# USB.net
KiCad netlist of a schematic drawn in Altium Designer
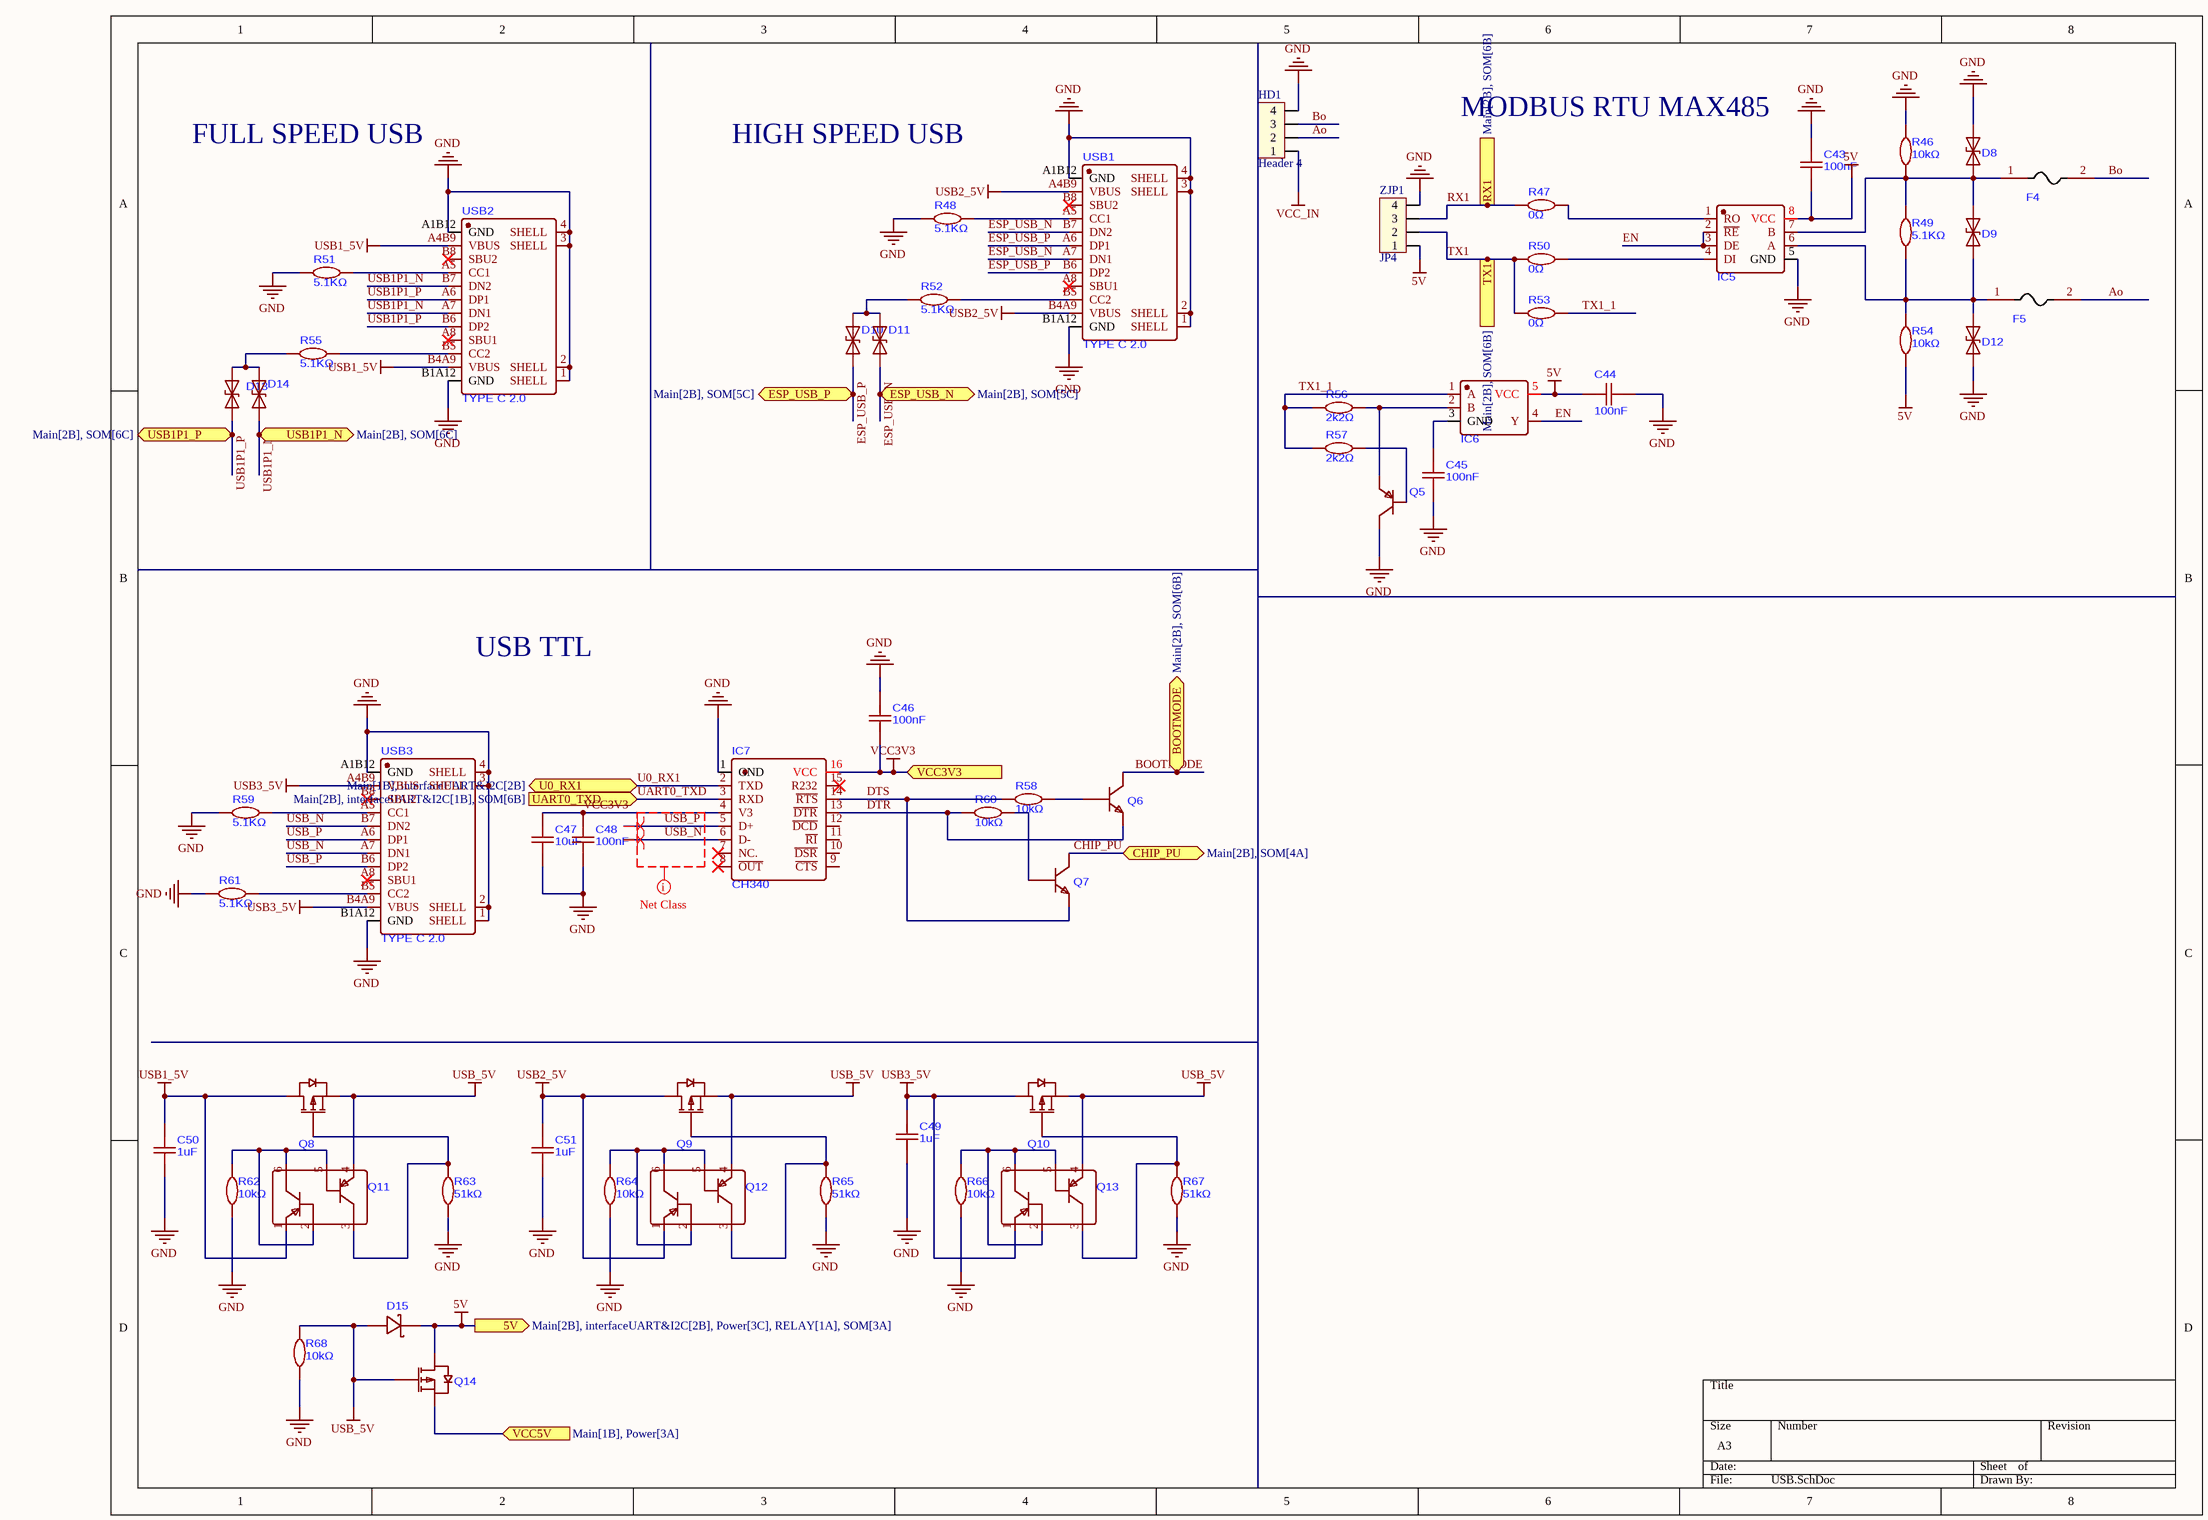
[diagram p0: USB.SchDoc]

(export (version "E")
  (design (tool "Eeschema 10.0.6"))
  (components
    (comp (ref "C43")
      (value "100nF")
      (footprint "C0603")
      (description "50V 100nF X7R ±10% 0603 Ceramic Capacitors ROHS")
      (libsource (lib "Schlib2") (part "CC0603KRX7R9BB104"))
    )
    (comp (ref "C44")
      (value "100nF")
      (footprint "C0603")
      (description "50V 100nF X7R ±10% 0603 Ceramic Capacitors ROHS")
      (libsource (lib "Schlib2") (part "CC0603KRX7R9BB104"))
    )
    (comp (ref "C45")
      (value "100nF")
      (footprint "C0603")
      (description "50V 100nF X7R ±10% 0603 Ceramic Capacitors ROHS")
      (libsource (lib "Schlib2") (part "CC0603KRX7R9BB104"))
    )
    (comp (ref "C46")
      (value "100nF")
      (footprint "C0603")
      (description "50V 100nF X7R ±10% 0603 Ceramic Capacitors ROHS")
      (libsource (lib "Schlib2") (part "CC0603KRX7R9BB104"))
    )
    (comp (ref "C47")
      (value "10uF")
      (footprint "C0603")
      (description "25V 10uF X5R ±20% 0603 Ceramic Capacitors ROHS")
      (libsource (lib "Schlib2") (part "CL10A106MA8NRNC"))
    )
    (comp (ref "C48")
      (value "100nF")
      (footprint "C0603")
      (description "50V 100nF X7R ±10% 0603 Ceramic Capacitors ROHS")
      (libsource (lib "Schlib2") (part "CC0603KRX7R9BB104"))
    )
    (comp (ref "C49")
      (value "1uF")
      (footprint "C0603")
      (description "25V 1uF X7R ±10% 0603 Ceramic Capacitors ROHS")
      (libsource (lib "Schlib2") (part "CL10B105KA8NNNC"))
    )
    (comp (ref "C50")
      (value "1uF")
      (footprint "C0603")
      (description "25V 1uF X7R ±10% 0603 Ceramic Capacitors ROHS")
      (libsource (lib "Schlib2") (part "CL10B105KA8NNNC"))
    )
    (comp (ref "C51")
      (value "1uF")
      (footprint "C0603")
      (description "25V 1uF X7R ±10% 0603 Ceramic Capacitors ROHS")
      (libsource (lib "Schlib2") (part "CL10B105KA8NNNC"))
    )
    (comp (ref "D8")
      (value "TVS DIODE 5VWM 18.6VC SOD-523")
      (footprint "SOD-523_L1.2-W0.8-LS1.6-BI")
      (description "9.4A@8/20us 18.6V 7.8V 5V SOD-523 TVS Diodes RoHS")
      (libsource (lib "Schlib2") (part "LESD5D5.0CT1G"))
    )
    (comp (ref "D9")
      (value "TVS DIODE 5VWM 18.6VC SOD-523")
      (footprint "SOD-523_L1.2-W0.8-LS1.6-BI")
      (description "9.4A@8/20us 18.6V 7.8V 5V SOD-523 TVS Diodes RoHS")
      (libsource (lib "Schlib2") (part "LESD5D5.0CT1G"))
    )
    (comp (ref "D10")
      (value "TVS DIODE 5VWM 18.6VC SOD-523")
      (footprint "SOD-523_L1.2-W0.8-LS1.6-BI")
      (description "9.4A@8/20us 18.6V 7.8V 5V SOD-523 TVS Diodes RoHS")
      (libsource (lib "Schlib2") (part "LESD5D5.0CT1G"))
    )
    (comp (ref "D11")
      (value "TVS DIODE 5VWM 18.6VC SOD-523")
      (footprint "SOD-523_L1.2-W0.8-LS1.6-BI")
      (description "9.4A@8/20us 18.6V 7.8V 5V SOD-523 TVS Diodes RoHS")
      (libsource (lib "Schlib2") (part "LESD5D5.0CT1G"))
    )
    (comp (ref "D12")
      (value "TVS DIODE 5VWM 18.6VC SOD-523")
      (footprint "SOD-523_L1.2-W0.8-LS1.6-BI")
      (description "9.4A@8/20us 18.6V 7.8V 5V SOD-523 TVS Diodes RoHS")
      (libsource (lib "Schlib2") (part "LESD5D5.0CT1G"))
    )
    (comp (ref "D13")
      (value "TVS DIODE 5VWM 18.6VC SOD-523")
      (footprint "SOD-523_L1.2-W0.8-LS1.6-BI")
      (description "9.4A@8/20us 18.6V 7.8V 5V SOD-523 TVS Diodes RoHS")
      (libsource (lib "Schlib2") (part "LESD5D5.0CT1G"))
    )
    (comp (ref "D14")
      (value "TVS DIODE 5VWM 18.6VC SOD-523")
      (footprint "SOD-523_L1.2-W0.8-LS1.6-BI")
      (description "9.4A@8/20us 18.6V 7.8V 5V SOD-523 TVS Diodes RoHS")
      (libsource (lib "Schlib2") (part "LESD5D5.0CT1G"))
    )
    (comp (ref "D15")
      (value "B540CQ-13-F")
      (footprint "SMC_L6.9-W5.9-LS7.9-RD")
      (description "40V 550mV@5A 5A SMC(DO-214AB) Single Diodes ROHS")
      (libsource (lib "Schlib2") (part "B540CQ-13-F"))
    )
    (comp (ref "F4")
      (value "PTC RESET FUSE 24V 100mA 0603")
      (footprint "F0603")
      (description "24V 100mA 40A 300mA 900mΩ 0603 PTC Resettable Fuses RoHS")
      (libsource (lib "Schlib2") (part "0603-010-24V"))
    )
    (comp (ref "F5")
      (value "PTC RESET FUSE 24V 100mA 0603")
      (footprint "F0603")
      (description "24V 100mA 40A 300mA 900mΩ 0603 PTC Resettable Fuses RoHS")
      (libsource (lib "Schlib2") (part "0603-010-24V"))
    )
    (comp (ref "HD1")
      (value "Header 4")
      (footprint "HED4")
      (description "Header 4 (Green)")
      (libsource (lib "syhaunguyen") (part "Hed4"))
    )
    (comp (ref "IC5")
      (value "Low-Power, Slew-Rate-Limited RS-485/RS-422 Transceivers")
      (footprint "SOP-8_L4.9-W3.9-P1.27-LS6.0-BL")
      (description "Transceiver 4.75V~5.25V SOIC-8 Drivers, Receivers, Transceivers RoHS")
      (libsource (lib "Schlib2") (part "MAX485ESA+T_C41365333"))
    )
    (comp (ref "IC6")
      (value "SINGLE 2-INPUT NAND GATE WITH SCHMITT-TRIGGER INPUTS")
      (footprint "SOT-23-5_L3.0-W1.7-P0.95-LS2.8-BL")
      (description "5ns@5V,50pF 10uA 1.65V~5.5V NAND Gate SOT-23-5 Gates and Inverters RoHS")
      (libsource (lib "Schlib2") (part "TP74LVC1G132S5"))
    )
    (comp (ref "IC7")
      (value "CH340")
      (footprint "SOP-16_L10.0-W3.9-P1.27-LS6.0-BL")
      (description "Transceiver USB 2.0 SOP-16 Interface Controllers RoHS")
      (libsource (lib "Schlib2") (part "CH340C"))
    )
    (comp (ref "Q5")
      (value "TRANS PNP 25V 1.5A SOT-23")
      (footprint "SOT-23-3_L2.9-W1.3-P1.90-LS2.4-BR")
      (description "300mW 25V 1.5A PNP SOT-23 Single Bipolar Transistors RoHS")
      (libsource (lib "Schlib2") (part "SS8550_C7420371"))
    )
    (comp (ref "Q6")
      (value "TRANS NPN 25V 0.5A SOT-23")
      (footprint "SOT-23-3_L2.9-W1.3-P1.90-LS2.4-BR")
      (description "300mW 25V 500mA NPN SOT-23 Single Bipolar Transistors RoHS")
      (libsource (lib "Schlib2") (part "S8050_C2828466"))
    )
    (comp (ref "Q7")
      (value "TRANS NPN 25V 0.5A SOT-23")
      (footprint "SOT-23-3_L2.9-W1.3-P1.90-LS2.4-BR")
      (description "300mW 25V 500mA NPN SOT-23 Single Bipolar Transistors RoHS")
      (libsource (lib "Schlib2") (part "S8050_C2828466"))
    )
    (comp (ref "Q8")
      (value "MOSFET P-CH 30V 4.3A SOT-23")
      (footprint "SOT-23-3_L2.9-W1.6-P1.90-LS2.8-BR")
      (description "30V 4.3A 48mΩ@10V 2.5V@250uA 1 P-Channel SOT-23 Single FETs, MOSFETs ROHS")
      (libsource (lib "Schlib2") (part "AO3407A"))
    )
    (comp (ref "Q9")
      (value "MOSFET P-CH 30V 4.3A SOT-23")
      (footprint "SOT-23-3_L2.9-W1.6-P1.90-LS2.8-BR")
      (description "30V 4.3A 48mΩ@10V 2.5V@250uA 1 P-Channel SOT-23 Single FETs, MOSFETs ROHS")
      (libsource (lib "Schlib2") (part "AO3407A"))
    )
    (comp (ref "Q10")
      (value "MOSFET P-CH 30V 4.3A SOT-23")
      (footprint "SOT-23-3_L2.9-W1.6-P1.90-LS2.8-BR")
      (description "30V 4.3A 48mΩ@10V 2.5V@250uA 1 P-Channel SOT-23 Single FETs, MOSFETs ROHS")
      (libsource (lib "Schlib2") (part "AO3407A"))
    )
    (comp (ref "Q11")
      (value "TRANS PNP 40V 200mA SOT-363")
      (footprint "SC-70-6_L2.2-W1.3-P0.65-LS2.1-TL")
      (description "40V 150mW 200mA PNP SOT-363 Single Bipolar Transistors RoHS")
      (libsource (lib "Schlib2") (part "LMBT3906DW1T1"))
    )
    (comp (ref "Q12")
      (value "TRANS PNP 40V 200mA SOT-363")
      (footprint "SC-70-6_L2.2-W1.3-P0.65-LS2.1-TL")
      (description "40V 150mW 200mA PNP SOT-363 Single Bipolar Transistors RoHS")
      (libsource (lib "Schlib2") (part "LMBT3906DW1T1"))
    )
    (comp (ref "Q13")
      (value "TRANS PNP 40V 200mA SOT-363")
      (footprint "SC-70-6_L2.2-W1.3-P0.65-LS2.1-TL")
      (description "40V 150mW 200mA PNP SOT-363 Single Bipolar Transistors RoHS")
      (libsource (lib "Schlib2") (part "LMBT3906DW1T1"))
    )
    (comp (ref "Q14")
      (value "MOSFET P-CH 30V 4.3A SOT-23")
      (footprint "SOT-23-3_L2.9-W1.6-P1.90-LS2.8-BR")
      (description "30V 4.3A 48mΩ@10V 2.5V@250uA 1 P-Channel SOT-23 Single FETs, MOSFETs ROHS")
      (libsource (lib "Schlib2") (part "AO3407A"))
    )
    (comp (ref "R46")
      (value "10kΩ")
      (footprint "R0603")
      (description "100mW 10kΩ 75V ±100ppm/℃ Thick Film Resistor ±1% 0603 Chip Resistor - Surface Mount ROHS")
      (libsource (lib "Schlib2") (part "RC0603FR-0710KL"))
    )
    (comp (ref "R47")
      (value "0Ω")
      (footprint "R0603")
      (description "100mW 0Ω 75V Thick Film Resistor ±5% 0603 Chip Resistor - Surface Mount RoHS")
      (libsource (lib "Schlib2") (part "RC0603JR-070RL"))
    )
    (comp (ref "R48")
      (value "5.1KΩ")
      (footprint "R0603")
      (description "100mW 5.1kΩ 75V ±100ppm/℃ Thick Film Resistor ±1% 0603 Chip Resistor - Surface Mount RoHS")
      (libsource (lib "Schlib2") (part "FRC0603F5101TS"))
    )
    (comp (ref "R49")
      (value "5.1KΩ")
      (footprint "R0603")
      (description "100mW 5.1kΩ 75V ±100ppm/℃ Thick Film Resistor ±1% 0603 Chip Resistor - Surface Mount RoHS")
      (libsource (lib "Schlib2") (part "FRC0603F5101TS"))
    )
    (comp (ref "R50")
      (value "0Ω")
      (footprint "R0603")
      (description "100mW 0Ω 75V Thick Film Resistor ±5% 0603 Chip Resistor - Surface Mount RoHS")
      (libsource (lib "Schlib2") (part "RC0603JR-070RL"))
    )
    (comp (ref "R51")
      (value "5.1KΩ")
      (footprint "R0603")
      (description "100mW 5.1kΩ 75V ±100ppm/℃ Thick Film Resistor ±1% 0603 Chip Resistor - Surface Mount RoHS")
      (libsource (lib "Schlib2") (part "FRC0603F5101TS"))
    )
    (comp (ref "R52")
      (value "5.1KΩ")
      (footprint "R0603")
      (description "100mW 5.1kΩ 75V ±100ppm/℃ Thick Film Resistor ±1% 0603 Chip Resistor - Surface Mount RoHS")
      (libsource (lib "Schlib2") (part "FRC0603F5101TS"))
    )
    (comp (ref "R53")
      (value "0Ω")
      (footprint "R0603")
      (description "100mW 0Ω 75V Thick Film Resistor ±5% 0603 Chip Resistor - Surface Mount RoHS")
      (libsource (lib "Schlib2") (part "RC0603JR-070RL"))
    )
    (comp (ref "R54")
      (value "10kΩ")
      (footprint "R0603")
      (description "100mW 10kΩ 75V ±100ppm/℃ Thick Film Resistor ±1% 0603 Chip Resistor - Surface Mount ROHS")
      (libsource (lib "Schlib2") (part "RC0603FR-0710KL"))
    )
    (comp (ref "R55")
      (value "5.1KΩ")
      (footprint "R0603")
      (description "100mW 5.1kΩ 75V ±100ppm/℃ Thick Film Resistor ±1% 0603 Chip Resistor - Surface Mount RoHS")
      (libsource (lib "Schlib2") (part "FRC0603F5101TS"))
    )
    (comp (ref "R56")
      (value "2k2Ω")
      (footprint "R0603")
      (description "100mW 2.2kΩ 75V ±100ppm/℃ Thick Film Resistor ±1% 0603 Chip Resistor - Surface Mount RoHS")
      (libsource (lib "Schlib2") (part "RC0603FR-072K2L"))
    )
    (comp (ref "R57")
      (value "2k2Ω")
      (footprint "R0603")
      (description "100mW 2.2kΩ 75V ±100ppm/℃ Thick Film Resistor ±1% 0603 Chip Resistor - Surface Mount RoHS")
      (libsource (lib "Schlib2") (part "RC0603FR-072K2L"))
    )
    (comp (ref "R58")
      (value "10kΩ")
      (footprint "R0603")
      (description "100mW 10kΩ 75V ±100ppm/℃ Thick Film Resistor ±1% 0603 Chip Resistor - Surface Mount ROHS")
      (libsource (lib "Schlib2") (part "RC0603FR-0710KL"))
    )
    (comp (ref "R59")
      (value "5.1KΩ")
      (footprint "R0603")
      (description "100mW 5.1kΩ 75V ±100ppm/℃ Thick Film Resistor ±1% 0603 Chip Resistor - Surface Mount RoHS")
      (libsource (lib "Schlib2") (part "FRC0603F5101TS"))
    )
    (comp (ref "R60")
      (value "10kΩ")
      (footprint "R0603")
      (description "100mW 10kΩ 75V ±100ppm/℃ Thick Film Resistor ±1% 0603 Chip Resistor - Surface Mount ROHS")
      (libsource (lib "Schlib2") (part "RC0603FR-0710KL"))
    )
    (comp (ref "R61")
      (value "5.1KΩ")
      (footprint "R0603")
      (description "100mW 5.1kΩ 75V ±100ppm/℃ Thick Film Resistor ±1% 0603 Chip Resistor - Surface Mount RoHS")
      (libsource (lib "Schlib2") (part "FRC0603F5101TS"))
    )
    (comp (ref "R62")
      (value "10kΩ")
      (footprint "R0603")
      (description "100mW 10kΩ 75V ±100ppm/℃ Thick Film Resistor ±1% 0603 Chip Resistor - Surface Mount ROHS")
      (libsource (lib "Schlib2") (part "RC0603FR-0710KL"))
    )
    (comp (ref "R63")
      (value "51kΩ")
      (footprint "R0603")
      (description "100mW 51kΩ 75V ±100ppm/℃ Thick Film Resistor ±1% 0603 Chip Resistor - Surface Mount RoHS")
      (libsource (lib "Schlib2") (part "RC0603FR-07100KL_1RC0603FR-0751KL"))
    )
    (comp (ref "R64")
      (value "10kΩ")
      (footprint "R0603")
      (description "100mW 10kΩ 75V ±100ppm/℃ Thick Film Resistor ±1% 0603 Chip Resistor - Surface Mount ROHS")
      (libsource (lib "Schlib2") (part "RC0603FR-0710KL"))
    )
    (comp (ref "R65")
      (value "51kΩ")
      (footprint "R0603")
      (description "100mW 51kΩ 75V ±100ppm/℃ Thick Film Resistor ±1% 0603 Chip Resistor - Surface Mount RoHS")
      (libsource (lib "Schlib2") (part "RC0603FR-07100KL_1RC0603FR-0751KL"))
    )
    (comp (ref "R66")
      (value "10kΩ")
      (footprint "R0603")
      (description "100mW 10kΩ 75V ±100ppm/℃ Thick Film Resistor ±1% 0603 Chip Resistor - Surface Mount ROHS")
      (libsource (lib "Schlib2") (part "RC0603FR-0710KL"))
    )
    (comp (ref "R67")
      (value "51kΩ")
      (footprint "R0603")
      (description "100mW 51kΩ 75V ±100ppm/℃ Thick Film Resistor ±1% 0603 Chip Resistor - Surface Mount RoHS")
      (libsource (lib "Schlib2") (part "RC0603FR-07100KL_1RC0603FR-0751KL"))
    )
    (comp (ref "R68")
      (value "10kΩ")
      (footprint "R0603")
      (description "100mW 10kΩ 75V ±100ppm/℃ Thick Film Resistor ±1% 0603 Chip Resistor - Surface Mount ROHS")
      (libsource (lib "Schlib2") (part "RC0603FR-0710KL"))
    )
    (comp (ref "USB1")
      (value "TYPE C 2.0")
      (footprint "USB-C-SMD_G-SWITCH_GT-USB-7010ASV")
      (description "USB 2.0 1 16P -40℃~+85℃ Type-C SMD USB, DVI, HDMI Connector Assemblies RoHS")
      (libsource (lib "Schlib2") (part "GT-USB-7010ASV"))
    )
    (comp (ref "USB2")
      (value "TYPE C 2.0")
      (footprint "USB-C-SMD_G-SWITCH_GT-USB-7010ASV")
      (description "USB 2.0 1 16P -40℃~+85℃ Type-C SMD USB, DVI, HDMI Connector Assemblies RoHS")
      (libsource (lib "Schlib2") (part "GT-USB-7010ASV"))
    )
    (comp (ref "USB3")
      (value "TYPE C 2.0")
      (footprint "USB-C-SMD_G-SWITCH_GT-USB-7010ASV")
      (description "USB 2.0 1 16P -40℃~+85℃ Type-C SMD USB, DVI, HDMI Connector Assemblies RoHS")
      (libsource (lib "Schlib2") (part "GT-USB-7010ASV"))
    )
    (comp (ref "ZJP1")
      (value "JP4")
      (footprint "CON4")
      (description "Connector 4")
      (libsource (lib "syhaunguyen") (part "Con4"))
    )
  )
  (nets
    (net (code "1") (name "/Ao") (class "Default")
      (node (ref "F5") (pin "2") (pinfunction "2_2") (pintype "passive"))
      (node (ref "HD1") (pin "2") (pinfunction "2_2") (pintype "passive"))
    )
    (net (code "2") (name "/BOOTMODE") (class "Default")
      (node (ref "Q6") (pin "3") (pinfunction "C_3") (pintype "passive"))
    )
    (net (code "3") (name "/Bo") (class "Default")
      (node (ref "F4") (pin "2") (pinfunction "2_2") (pintype "passive"))
      (node (ref "HD1") (pin "3") (pinfunction "3_3") (pintype "passive"))
    )
    (net (code "4") (name "/CHIP_PU") (class "Default")
      (node (ref "Q7") (pin "3") (pinfunction "C_3") (pintype "passive"))
    )
    (net (code "5") (name "/DTR") (class "Default")
      (node (ref "IC7") (pin "13") (pinfunction "~{DTR}_13") (pintype "passive"))
      (node (ref "Q6") (pin "2") (pinfunction "E_2") (pintype "passive"))
      (node (ref "R60") (pin "1") (pinfunction "1_1") (pintype "passive"))
    )
    (net (code "6") (name "/DTS") (class "Default")
      (node (ref "IC7") (pin "14") (pinfunction "~{RTS}_14") (pintype "passive"))
      (node (ref "Q7") (pin "2") (pinfunction "E_2") (pintype "passive"))
      (node (ref "R58") (pin "1") (pinfunction "1_1") (pintype "passive"))
    )
    (net (code "7") (name "/EN") (class "Default")
      (node (ref "IC5") (pin "2") (pinfunction "~{RE}_2") (pintype "passive"))
      (node (ref "IC5") (pin "3") (pinfunction "DE_3") (pintype "passive"))
      (node (ref "IC6") (pin "4") (pinfunction "Y_4") (pintype "passive"))
    )
    (net (code "8") (name "/ESP_USB_N") (class "Default")
      (node (ref "D11") (pin "1") (pinfunction "K_1") (pintype "passive"))
      (node (ref "USB1") (pin "A7") (pinfunction "DN1_A7") (pintype "passive"))
      (node (ref "USB1") (pin "B7") (pinfunction "DN2_B7") (pintype "passive"))
    )
    (net (code "9") (name "/ESP_USB_P") (class "Default")
      (node (ref "D10") (pin "1") (pinfunction "K_1") (pintype "passive"))
      (node (ref "USB1") (pin "A6") (pinfunction "DP1_A6") (pintype "passive"))
      (node (ref "USB1") (pin "B6") (pinfunction "DP2_B6") (pintype "passive"))
    )
    (net (code "10") (name "/RX1") (class "Default")
      (node (ref "R47") (pin "1") (pinfunction "1_1") (pintype "passive"))
      (node (ref "ZJP1") (pin "3") (pinfunction "3_3") (pintype "passive"))
    )
    (net (code "11") (name "/TX1") (class "Default")
      (node (ref "R50") (pin "1") (pinfunction "1_1") (pintype "passive"))
      (node (ref "R53") (pin "1") (pinfunction "1_1") (pintype "passive"))
      (node (ref "ZJP1") (pin "2") (pinfunction "2_2") (pintype "passive"))
    )
    (net (code "12") (name "/TX1_1") (class "Default")
      (node (ref "IC6") (pin "1") (pinfunction "A_1") (pintype "passive"))
      (node (ref "R53") (pin "2") (pinfunction "2_2") (pintype "passive"))
      (node (ref "R56") (pin "2") (pinfunction "2_2") (pintype "passive"))
      (node (ref "R57") (pin "1") (pinfunction "1_1") (pintype "passive"))
    )
    (net (code "13") (name "/U0_RX1") (class "Default")
      (node (ref "IC7") (pin "2") (pinfunction "TXD_2") (pintype "passive"))
    )
    (net (code "14") (name "/UART0_TXD") (class "Default")
      (node (ref "IC7") (pin "3") (pinfunction "RXD_3") (pintype "passive"))
    )
    (net (code "15") (name "/USB1P1_N") (class "Default")
      (node (ref "D14") (pin "1") (pinfunction "K_1") (pintype "passive"))
      (node (ref "USB2") (pin "A7") (pinfunction "DN1_A7") (pintype "passive"))
      (node (ref "USB2") (pin "B7") (pinfunction "DN2_B7") (pintype "passive"))
    )
    (net (code "16") (name "/USB1P1_P") (class "Default")
      (node (ref "D13") (pin "1") (pinfunction "K_1") (pintype "passive"))
      (node (ref "USB2") (pin "A6") (pinfunction "DP1_A6") (pintype "passive"))
      (node (ref "USB2") (pin "B6") (pinfunction "DP2_B6") (pintype "passive"))
    )
    (net (code "17") (name "/USB_N") (class "Default")
      (node (ref "IC7") (pin "6") (pinfunction "D-_6") (pintype "passive"))
      (node (ref "USB3") (pin "A7") (pinfunction "DN1_A7") (pintype "passive"))
      (node (ref "USB3") (pin "B7") (pinfunction "DN2_B7") (pintype "passive"))
    )
    (net (code "18") (name "/USB_P") (class "Default")
      (node (ref "IC7") (pin "5") (pinfunction "D+_5") (pintype "passive"))
      (node (ref "USB3") (pin "A6") (pinfunction "DP1_A6") (pintype "passive"))
      (node (ref "USB3") (pin "B6") (pinfunction "DP2_B6") (pintype "passive"))
    )
    (net (code "19") (name "/VCC5V") (class "Default")
      (node (ref "Q14") (pin "2") (pinfunction "S_2") (pintype "passive"))
    )
    (net (code "20") (name "5V") (class "Default")
      (node (ref "C43") (pin "1") (pinfunction "1_1") (pintype "passive"))
      (node (ref "C44") (pin "2") (pinfunction "2_2") (pintype "passive"))
      (node (ref "D15") (pin "1") (pinfunction "C_1") (pintype "passive"))
      (node (ref "IC5") (pin "8") (pinfunction "VCC_8") (pintype "passive"))
      (node (ref "IC6") (pin "5") (pinfunction "VCC_5") (pintype "passive"))
      (node (ref "Q14") (pin "3") (pinfunction "D_3") (pintype "passive"))
      (node (ref "R54") (pin "1") (pinfunction "1_1") (pintype "passive"))
      (node (ref "ZJP1") (pin "1") (pinfunction "1_1") (pintype "passive"))
    )
    (net (code "21") (name "GND") (class "Default")
      (node (ref "C43") (pin "2") (pinfunction "2_2") (pintype "passive"))
      (node (ref "C44") (pin "1") (pinfunction "1_1") (pintype "passive"))
      (node (ref "C45") (pin "1") (pinfunction "1_1") (pintype "passive"))
      (node (ref "C46") (pin "2") (pinfunction "2_2") (pintype "passive"))
      (node (ref "C47") (pin "1") (pinfunction "1_1") (pintype "passive"))
      (node (ref "C48") (pin "1") (pinfunction "1_1") (pintype "passive"))
      (node (ref "C49") (pin "1") (pinfunction "1_1") (pintype "passive"))
      (node (ref "C50") (pin "1") (pinfunction "1_1") (pintype "passive"))
      (node (ref "C51") (pin "1") (pinfunction "1_1") (pintype "passive"))
      (node (ref "D12") (pin "1") (pinfunction "K_1") (pintype "passive"))
      (node (ref "D8") (pin "2") (pinfunction "A_2") (pintype "passive"))
      (node (ref "HD1") (pin "4") (pinfunction "4_4") (pintype "passive"))
      (node (ref "IC5") (pin "5") (pinfunction "GND_5") (pintype "passive"))
      (node (ref "IC7") (pin "1") (pinfunction "GND_1") (pintype "passive"))
      (node (ref "Q5") (pin "3") (pinfunction "C_3") (pintype "passive"))
      (node (ref "R46") (pin "2") (pinfunction "2_2") (pintype "passive"))
      (node (ref "R48") (pin "1") (pinfunction "1_1") (pintype "passive"))
      (node (ref "R51") (pin "1") (pinfunction "1_1") (pintype "passive"))
      (node (ref "R59") (pin "1") (pinfunction "1_1") (pintype "passive"))
      (node (ref "R61") (pin "1") (pinfunction "1_1") (pintype "passive"))
      (node (ref "R62") (pin "1") (pinfunction "1_1") (pintype "passive"))
      (node (ref "R63") (pin "1") (pinfunction "1_1") (pintype "passive"))
      (node (ref "R64") (pin "1") (pinfunction "1_1") (pintype "passive"))
      (node (ref "R65") (pin "1") (pinfunction "1_1") (pintype "passive"))
      (node (ref "R66") (pin "1") (pinfunction "1_1") (pintype "passive"))
      (node (ref "R67") (pin "1") (pinfunction "1_1") (pintype "passive"))
      (node (ref "R68") (pin "1") (pinfunction "1_1") (pintype "passive"))
      (node (ref "USB1") (pin "1") (pinfunction "SHELL_1") (pintype "passive"))
      (node (ref "USB1") (pin "2") (pinfunction "SHELL_2") (pintype "passive"))
      (node (ref "USB1") (pin "3") (pinfunction "SHELL_3") (pintype "passive"))
      (node (ref "USB1") (pin "4") (pinfunction "SHELL_4") (pintype "passive"))
      (node (ref "USB1") (pin "A1B12") (pinfunction "GND_A1B12") (pintype "passive"))
      (node (ref "USB1") (pin "B1A12") (pinfunction "GND_B1A12") (pintype "passive"))
      (node (ref "USB2") (pin "1") (pinfunction "SHELL_1") (pintype "passive"))
      (node (ref "USB2") (pin "2") (pinfunction "SHELL_2") (pintype "passive"))
      (node (ref "USB2") (pin "3") (pinfunction "SHELL_3") (pintype "passive"))
      (node (ref "USB2") (pin "4") (pinfunction "SHELL_4") (pintype "passive"))
      (node (ref "USB2") (pin "A1B12") (pinfunction "GND_A1B12") (pintype "passive"))
      (node (ref "USB2") (pin "B1A12") (pinfunction "GND_B1A12") (pintype "passive"))
      (node (ref "USB3") (pin "1") (pinfunction "SHELL_1") (pintype "passive"))
      (node (ref "USB3") (pin "2") (pinfunction "SHELL_2") (pintype "passive"))
      (node (ref "USB3") (pin "3") (pinfunction "SHELL_3") (pintype "passive"))
      (node (ref "USB3") (pin "4") (pinfunction "SHELL_4") (pintype "passive"))
      (node (ref "USB3") (pin "A1B12") (pinfunction "GND_A1B12") (pintype "passive"))
      (node (ref "USB3") (pin "B1A12") (pinfunction "GND_B1A12") (pintype "passive"))
      (node (ref "ZJP1") (pin "4") (pinfunction "4_4") (pintype "passive"))
    )
    (net (code "22") (name "Net-(D8-K)") (class "Default")
      (node (ref "D8") (pin "1") (pinfunction "K_1") (pintype "passive"))
      (node (ref "D9") (pin "2") (pinfunction "A_2") (pintype "passive"))
      (node (ref "F4") (pin "1") (pinfunction "1_1") (pintype "passive"))
      (node (ref "IC5") (pin "7") (pinfunction "B_7") (pintype "passive"))
      (node (ref "R46") (pin "1") (pinfunction "1_1") (pintype "passive"))
      (node (ref "R49") (pin "2") (pinfunction "2_2") (pintype "passive"))
    )
    (net (code "23") (name "Net-(D10-A)") (class "Default")
      (node (ref "D10") (pin "2") (pinfunction "A_2") (pintype "passive"))
      (node (ref "D11") (pin "2") (pinfunction "A_2") (pintype "passive"))
      (node (ref "R52") (pin "1") (pinfunction "1_1") (pintype "passive"))
    )
    (net (code "24") (name "Net-(D12-A)") (class "Default")
      (node (ref "D12") (pin "2") (pinfunction "A_2") (pintype "passive"))
      (node (ref "D9") (pin "1") (pinfunction "K_1") (pintype "passive"))
      (node (ref "F5") (pin "1") (pinfunction "1_1") (pintype "passive"))
      (node (ref "IC5") (pin "6") (pinfunction "A_6") (pintype "passive"))
      (node (ref "R49") (pin "1") (pinfunction "1_1") (pintype "passive"))
      (node (ref "R54") (pin "2") (pinfunction "2_2") (pintype "passive"))
    )
    (net (code "25") (name "Net-(D13-A)") (class "Default")
      (node (ref "D13") (pin "2") (pinfunction "A_2") (pintype "passive"))
      (node (ref "D14") (pin "2") (pinfunction "A_2") (pintype "passive"))
      (node (ref "R55") (pin "1") (pinfunction "1_1") (pintype "passive"))
    )
    (net (code "26") (name "Net-(IC5-DI)") (class "Default")
      (node (ref "IC5") (pin "4") (pinfunction "DI_4") (pintype "passive"))
      (node (ref "R50") (pin "2") (pinfunction "2_2") (pintype "passive"))
    )
    (net (code "27") (name "Net-(IC5-RO)") (class "Default")
      (node (ref "IC5") (pin "1") (pinfunction "RO_1") (pintype "passive"))
      (node (ref "R47") (pin "2") (pinfunction "2_2") (pintype "passive"))
    )
    (net (code "28") (name "Net-(IC6-B)") (class "Default")
      (node (ref "IC6") (pin "2") (pinfunction "B_2") (pintype "passive"))
      (node (ref "Q5") (pin "2") (pinfunction "E_2") (pintype "passive"))
      (node (ref "R56") (pin "1") (pinfunction "1_1") (pintype "passive"))
    )
    (net (code "29") (name "Net-(IC6-GND)") (class "Default")
      (node (ref "C45") (pin "2") (pinfunction "2_2") (pintype "passive"))
      (node (ref "IC6") (pin "3") (pinfunction "GND_3") (pintype "passive"))
    )
    (net (code "30") (name "Net-(Q5-B)") (class "Default")
      (node (ref "Q5") (pin "1") (pinfunction "B_1") (pintype "passive"))
      (node (ref "R57") (pin "2") (pinfunction "2_2") (pintype "passive"))
    )
    (net (code "31") (name "Net-(Q6-B)") (class "Default")
      (node (ref "Q6") (pin "1") (pinfunction "B_1") (pintype "passive"))
      (node (ref "R58") (pin "2") (pinfunction "2_2") (pintype "passive"))
    )
    (net (code "32") (name "Net-(Q7-B)") (class "Default")
      (node (ref "Q7") (pin "1") (pinfunction "B_1") (pintype "passive"))
      (node (ref "R60") (pin "2") (pinfunction "2_2") (pintype "passive"))
    )
    (net (code "33") (name "Net-(Q10-G)") (class "Default")
      (node (ref "Q10") (pin "1") (pinfunction "G_1") (pintype "passive"))
      (node (ref "Q13") (pin "3") (pinfunction "C1_3") (pintype "passive"))
      (node (ref "R67") (pin "2") (pinfunction "2_2") (pintype "passive"))
    )
    (net (code "34") (name "Net-(Q11-B1)") (class "Default")
      (node (ref "Q11") (pin "2") (pinfunction "B2_2") (pintype "passive"))
      (node (ref "Q11") (pin "5") (pinfunction "B1_5") (pintype "passive"))
      (node (ref "Q11") (pin "6") (pinfunction "C2_6") (pintype "passive"))
      (node (ref "R62") (pin "2") (pinfunction "2_2") (pintype "passive"))
    )
    (net (code "35") (name "Net-(Q11-C1)") (class "Default")
      (node (ref "Q11") (pin "3") (pinfunction "C1_3") (pintype "passive"))
      (node (ref "Q8") (pin "1") (pinfunction "G_1") (pintype "passive"))
      (node (ref "R63") (pin "2") (pinfunction "2_2") (pintype "passive"))
    )
    (net (code "36") (name "Net-(Q12-B1)") (class "Default")
      (node (ref "Q12") (pin "2") (pinfunction "B2_2") (pintype "passive"))
      (node (ref "Q12") (pin "5") (pinfunction "B1_5") (pintype "passive"))
      (node (ref "Q12") (pin "6") (pinfunction "C2_6") (pintype "passive"))
      (node (ref "R64") (pin "2") (pinfunction "2_2") (pintype "passive"))
    )
    (net (code "37") (name "Net-(Q12-C1)") (class "Default")
      (node (ref "Q12") (pin "3") (pinfunction "C1_3") (pintype "passive"))
      (node (ref "Q9") (pin "1") (pinfunction "G_1") (pintype "passive"))
      (node (ref "R65") (pin "2") (pinfunction "2_2") (pintype "passive"))
    )
    (net (code "38") (name "Net-(Q13-B1)") (class "Default")
      (node (ref "Q13") (pin "2") (pinfunction "B2_2") (pintype "passive"))
      (node (ref "Q13") (pin "5") (pinfunction "B1_5") (pintype "passive"))
      (node (ref "Q13") (pin "6") (pinfunction "C2_6") (pintype "passive"))
      (node (ref "R66") (pin "2") (pinfunction "2_2") (pintype "passive"))
    )
    (net (code "39") (name "Net-(USB1-CC1)") (class "Default")
      (node (ref "R48") (pin "2") (pinfunction "2_2") (pintype "passive"))
      (node (ref "USB1") (pin "A5") (pinfunction "CC1_A5") (pintype "passive"))
    )
    (net (code "40") (name "Net-(USB1-CC2)") (class "Default")
      (node (ref "R52") (pin "2") (pinfunction "2_2") (pintype "passive"))
      (node (ref "USB1") (pin "B5") (pinfunction "CC2_B5") (pintype "passive"))
    )
    (net (code "41") (name "Net-(USB2-CC1)") (class "Default")
      (node (ref "R51") (pin "2") (pinfunction "2_2") (pintype "passive"))
      (node (ref "USB2") (pin "A5") (pinfunction "CC1_A5") (pintype "passive"))
    )
    (net (code "42") (name "Net-(USB2-CC2)") (class "Default")
      (node (ref "R55") (pin "2") (pinfunction "2_2") (pintype "passive"))
      (node (ref "USB2") (pin "B5") (pinfunction "CC2_B5") (pintype "passive"))
    )
    (net (code "43") (name "Net-(USB3-CC1)") (class "Default")
      (node (ref "R59") (pin "2") (pinfunction "2_2") (pintype "passive"))
      (node (ref "USB3") (pin "A5") (pinfunction "CC1_A5") (pintype "passive"))
    )
    (net (code "44") (name "Net-(USB3-CC2)") (class "Default")
      (node (ref "R61") (pin "2") (pinfunction "2_2") (pintype "passive"))
      (node (ref "USB3") (pin "B5") (pinfunction "CC2_B5") (pintype "passive"))
    )
    (net (code "45") (name "USB1_5V") (class "Default")
      (node (ref "C50") (pin "2") (pinfunction "2_2") (pintype "passive"))
      (node (ref "Q11") (pin "1") (pinfunction "E2_1") (pintype "passive"))
      (node (ref "Q8") (pin "3") (pinfunction "D_3") (pintype "passive"))
      (node (ref "USB2") (pin "A4B9") (pinfunction "VBUS_A4B9") (pintype "passive"))
      (node (ref "USB2") (pin "B4A9") (pinfunction "VBUS_B4A9") (pintype "passive"))
    )
    (net (code "46") (name "USB2_5V") (class "Default")
      (node (ref "C51") (pin "2") (pinfunction "2_2") (pintype "passive"))
      (node (ref "Q12") (pin "1") (pinfunction "E2_1") (pintype "passive"))
      (node (ref "Q9") (pin "3") (pinfunction "D_3") (pintype "passive"))
      (node (ref "USB1") (pin "A4B9") (pinfunction "VBUS_A4B9") (pintype "passive"))
      (node (ref "USB1") (pin "B4A9") (pinfunction "VBUS_B4A9") (pintype "passive"))
    )
    (net (code "47") (name "USB3_5V") (class "Default")
      (node (ref "C49") (pin "2") (pinfunction "2_2") (pintype "passive"))
      (node (ref "Q10") (pin "3") (pinfunction "D_3") (pintype "passive"))
      (node (ref "Q13") (pin "1") (pinfunction "E2_1") (pintype "passive"))
      (node (ref "USB3") (pin "A4B9") (pinfunction "VBUS_A4B9") (pintype "passive"))
      (node (ref "USB3") (pin "B4A9") (pinfunction "VBUS_B4A9") (pintype "passive"))
    )
    (net (code "48") (name "USB_5V") (class "Default")
      (node (ref "D15") (pin "2") (pinfunction "A_2") (pintype "passive"))
      (node (ref "Q10") (pin "2") (pinfunction "S_2") (pintype "passive"))
      (node (ref "Q11") (pin "4") (pinfunction "E1_4") (pintype "passive"))
      (node (ref "Q12") (pin "4") (pinfunction "E1_4") (pintype "passive"))
      (node (ref "Q13") (pin "4") (pinfunction "E1_4") (pintype "passive"))
      (node (ref "Q14") (pin "1") (pinfunction "G_1") (pintype "passive"))
      (node (ref "Q8") (pin "2") (pinfunction "S_2") (pintype "passive"))
      (node (ref "Q9") (pin "2") (pinfunction "S_2") (pintype "passive"))
      (node (ref "R68") (pin "2") (pinfunction "2_2") (pintype "passive"))
    )
    (net (code "49") (name "VCC3V3") (class "Default")
      (node (ref "C46") (pin "1") (pinfunction "1_1") (pintype "passive"))
      (node (ref "C47") (pin "2") (pinfunction "2_2") (pintype "passive"))
      (node (ref "C48") (pin "2") (pinfunction "2_2") (pintype "passive"))
      (node (ref "IC7") (pin "16") (pinfunction "VCC_16") (pintype "passive"))
      (node (ref "IC7") (pin "4") (pinfunction "V3_4") (pintype "passive"))
    )
    (net (code "50") (name "VCC_IN") (class "Default")
      (node (ref "HD1") (pin "1") (pinfunction "1_1") (pintype "passive"))
    )
    (net (code "51") (name "unconnected-(IC7-NC.-Pad7)") (class "Default")
      (node (ref "IC7") (pin "7") (pinfunction "NC._7") (pintype "passive+no_connect"))
    )
    (net (code "52") (name "unconnected-(IC7-R232-Pad15)") (class "Default")
      (node (ref "IC7") (pin "15") (pinfunction "R232_15") (pintype "passive+no_connect"))
    )
    (net (code "53") (name "unconnected-(IC7-~{CTS}-Pad9)") (class "Default")
      (node (ref "IC7") (pin "9") (pinfunction "~{CTS}_9") (pintype "passive"))
    )
    (net (code "54") (name "unconnected-(IC7-~{DCD}-Pad12)") (class "Default")
      (node (ref "IC7") (pin "12") (pinfunction "~{DCD}_12") (pintype "passive"))
    )
    (net (code "55") (name "unconnected-(IC7-~{DSR}-Pad10)") (class "Default")
      (node (ref "IC7") (pin "10") (pinfunction "~{DSR}_10") (pintype "passive"))
    )
    (net (code "56") (name "unconnected-(IC7-~{OUT}-Pad8)") (class "Default")
      (node (ref "IC7") (pin "8") (pinfunction "~{OUT}_8") (pintype "passive+no_connect"))
    )
    (net (code "57") (name "unconnected-(IC7-~{RI}-Pad11)") (class "Default")
      (node (ref "IC7") (pin "11") (pinfunction "~{RI}_11") (pintype "passive"))
    )
    (net (code "58") (name "unconnected-(USB1-SBU1-PadA8)") (class "Default")
      (node (ref "USB1") (pin "A8") (pinfunction "SBU1_A8") (pintype "passive+no_connect"))
    )
    (net (code "59") (name "unconnected-(USB1-SBU2-PadB8)") (class "Default")
      (node (ref "USB1") (pin "B8") (pinfunction "SBU2_B8") (pintype "passive+no_connect"))
    )
    (net (code "60") (name "unconnected-(USB2-SBU1-PadA8)") (class "Default")
      (node (ref "USB2") (pin "A8") (pinfunction "SBU1_A8") (pintype "passive+no_connect"))
    )
    (net (code "61") (name "unconnected-(USB2-SBU2-PadB8)") (class "Default")
      (node (ref "USB2") (pin "B8") (pinfunction "SBU2_B8") (pintype "passive+no_connect"))
    )
    (net (code "62") (name "unconnected-(USB3-SBU1-PadA8)") (class "Default")
      (node (ref "USB3") (pin "A8") (pinfunction "SBU1_A8") (pintype "passive+no_connect"))
    )
    (net (code "63") (name "unconnected-(USB3-SBU2-PadB8)") (class "Default")
      (node (ref "USB3") (pin "B8") (pinfunction "SBU2_B8") (pintype "passive+no_connect"))
    )
  )
)
